# SMARTBALL_v2_1.net
KiCad netlist of a schematic drawn in EAGLE
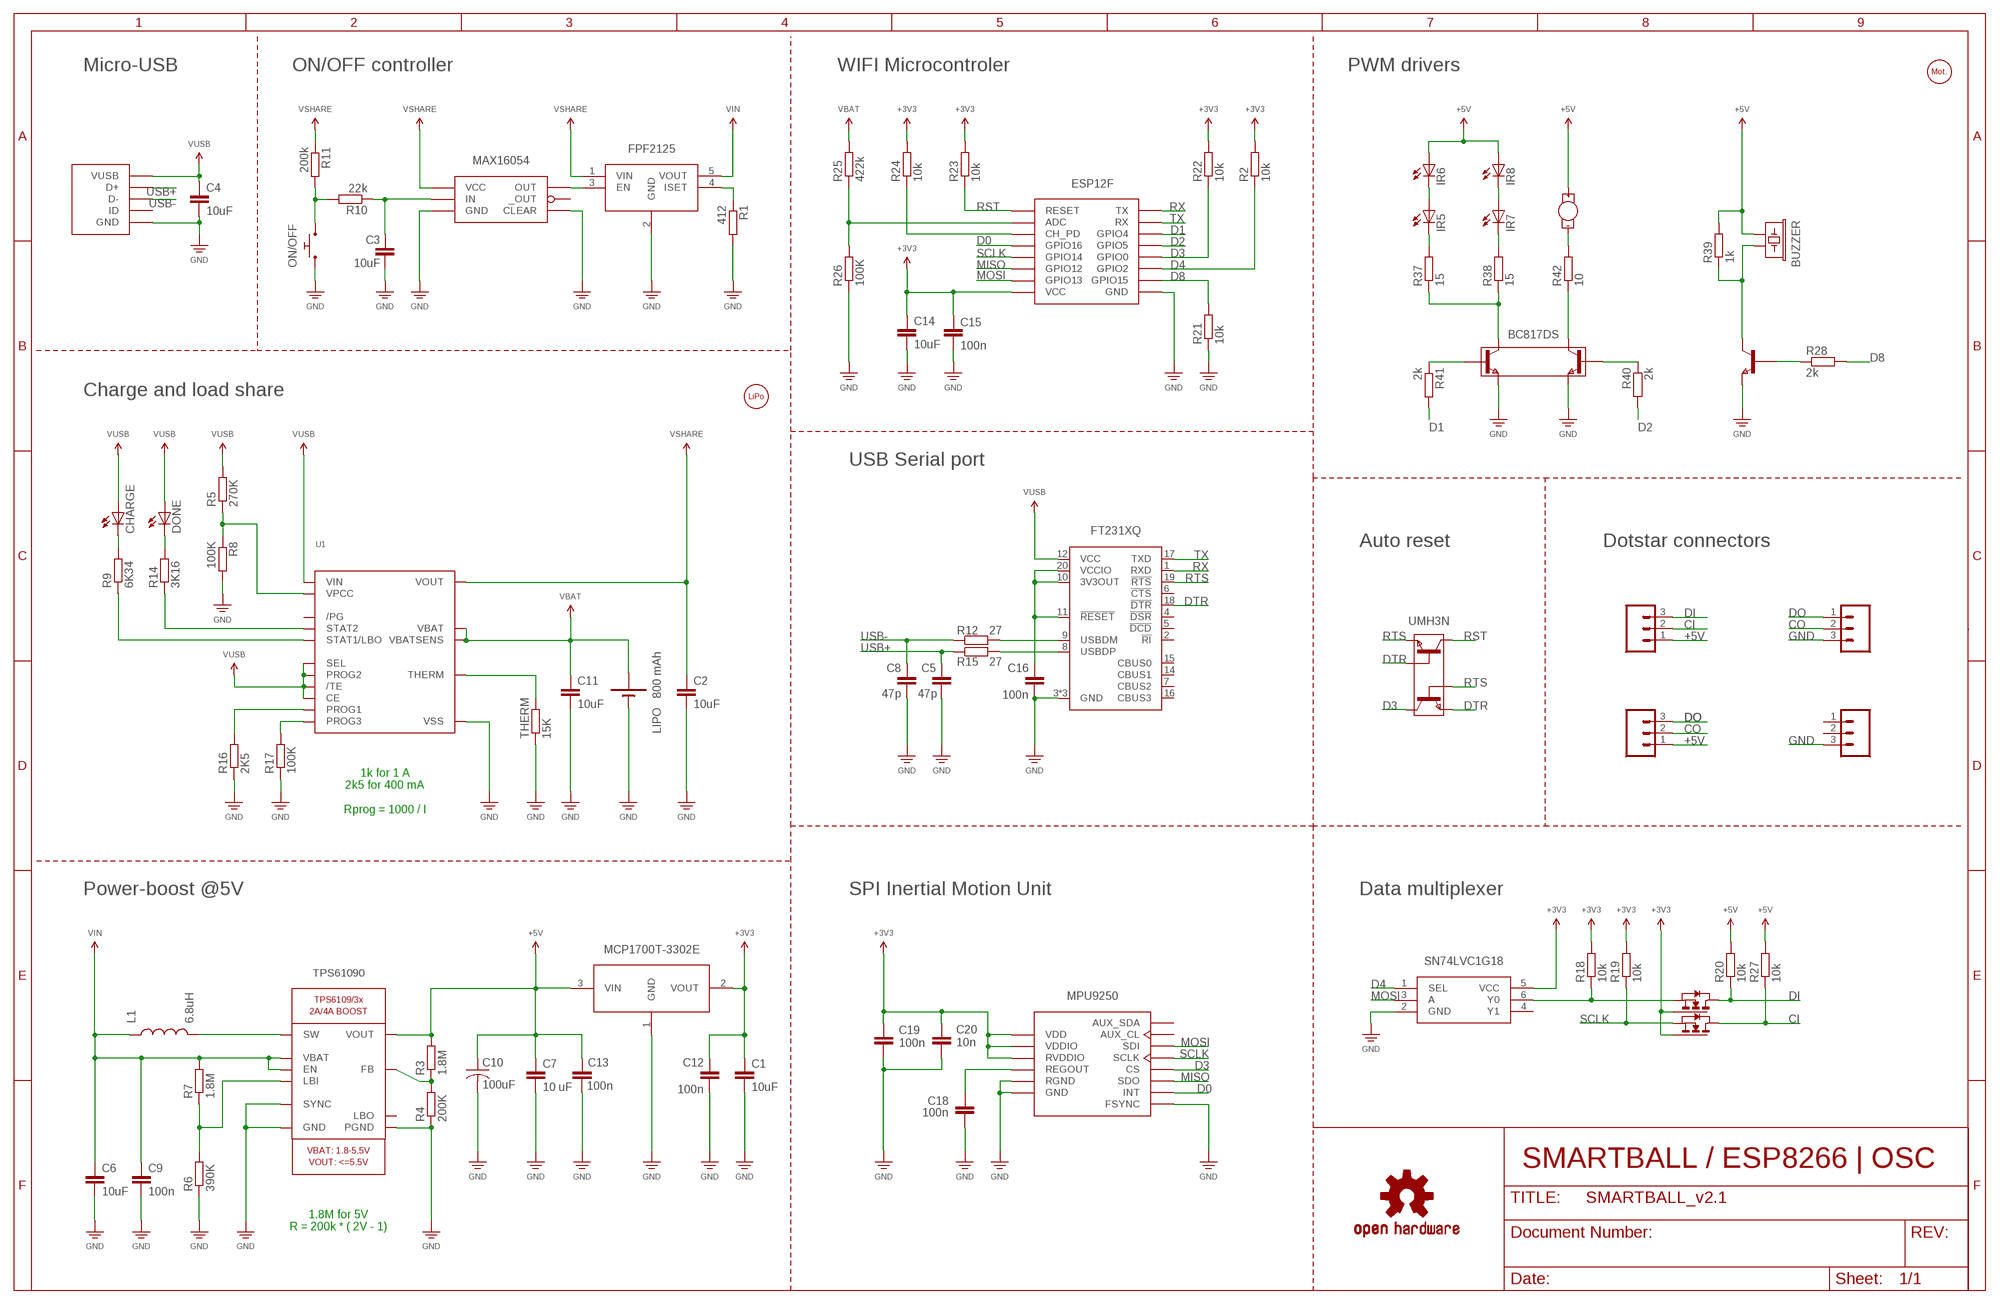
[diagram p0: schematic, sheet 1]

(export (version "E")
  (design (tool "Eeschema 10.0.6"))
  (components
    (comp (ref "BC817DS")
      (value "SOT_BC817DS")
      (footprint "eagle-import:SOT457R_PHILIPS")
      (libsource (lib "eagle-import") (part "SOT_BC817DS"))
    )
    (comp (ref "BUZZER")
      (value "BUZZER_PKMCS0909E4000-R1")
      (footprint "eagle-import:BUZZER_PKMCS0909E4000-R1")
      (libsource (lib "eagle-import") (part "BUZZER_PKMCS0909E4000-R1"))
    )
    (comp (ref "C1")
      (value "10uF")
      (footprint "eagle-import:C0603")
      (libsource (lib "eagle-import") (part "CAP_CERAMICC0603K"))
    )
    (comp (ref "C2")
      (value "10uF")
      (footprint "eagle-import:C0603")
      (libsource (lib "eagle-import") (part "CAP_CERAMICC0603K"))
    )
    (comp (ref "C3")
      (value "10uF")
      (footprint "eagle-import:C0603")
      (libsource (lib "eagle-import") (part "CAP_CERAMICC0603K"))
    )
    (comp (ref "C4")
      (value "10uF")
      (footprint "eagle-import:C0603")
      (libsource (lib "eagle-import") (part "CAP_CERAMICC0603K"))
    )
    (comp (ref "C5")
      (value "47p")
      (footprint "eagle-import:C0603")
      (libsource (lib "eagle-import") (part "CAP_CERAMICC0603K"))
    )
    (comp (ref "C6")
      (value "10uF")
      (footprint "eagle-import:C0603")
      (libsource (lib "eagle-import") (part "CAP_CERAMICC0603K"))
    )
    (comp (ref "C7")
      (value "10 uF")
      (footprint "eagle-import:C0603")
      (libsource (lib "eagle-import") (part "CAP_CERAMICC0603K"))
    )
    (comp (ref "C8")
      (value "47p")
      (footprint "eagle-import:C0603")
      (libsource (lib "eagle-import") (part "CAP_CERAMICC0603K"))
    )
    (comp (ref "C9")
      (value "100n")
      (footprint "eagle-import:C0603")
      (libsource (lib "eagle-import") (part "CAP_CERAMICC0603K"))
    )
    (comp (ref "C10")
      (value "100uF")
      (footprint "eagle-import:C1210")
      (libsource (lib "eagle-import") (part "CAP_TANTALUMC1210"))
    )
    (comp (ref "C11")
      (value "10uF")
      (footprint "eagle-import:C0603")
      (libsource (lib "eagle-import") (part "CAP_CERAMICC0603K"))
    )
    (comp (ref "C12")
      (value "100n")
      (footprint "eagle-import:C0603")
      (libsource (lib "eagle-import") (part "CAP_CERAMICC0603K"))
    )
    (comp (ref "C13")
      (value "100n")
      (footprint "eagle-import:C0603")
      (libsource (lib "eagle-import") (part "CAP_CERAMICC0603K"))
    )
    (comp (ref "C14")
      (value "10uF")
      (footprint "eagle-import:C0603")
      (libsource (lib "eagle-import") (part "CAP_CERAMICC0603K"))
    )
    (comp (ref "C15")
      (value "100n")
      (footprint "eagle-import:C0603")
      (libsource (lib "eagle-import") (part "CAP_CERAMICC0603K"))
    )
    (comp (ref "C16")
      (value "100n")
      (footprint "eagle-import:C0603")
      (libsource (lib "eagle-import") (part "CAP_CERAMICC0603K"))
    )
    (comp (ref "C18")
      (value "100n")
      (footprint "eagle-import:C0603")
      (libsource (lib "eagle-import") (part "CAP_CERAMICC0603K"))
    )
    (comp (ref "C19")
      (value "100n")
      (footprint "eagle-import:C0603")
      (libsource (lib "eagle-import") (part "CAP_CERAMICC0603K"))
    )
    (comp (ref "C20")
      (value "10n")
      (footprint "eagle-import:C0603")
      (libsource (lib "eagle-import") (part "CAP_CERAMICC0603K"))
    )
    (comp (ref "CHARGE")
      (value "LED_KINGBRIGHT_16X08")
      (footprint "eagle-import:LED_KINGBRIGHT_16X08")
      (libsource (lib "eagle-import") (part "LED_KINGBRIGHT_16X08"))
    )
    (comp (ref "DONE")
      (value "LED_KINGBRIGHT_16X08")
      (footprint "eagle-import:LED_KINGBRIGHT_16X08")
      (libsource (lib "eagle-import") (part "LED_KINGBRIGHT_16X08"))
    )
    (comp (ref "ESP12F")
      (value "µP_ESP12")
      (footprint "eagle-import:µP_ESP12")
      (libsource (lib "eagle-import") (part "µP_ESP12"))
    )
    (comp (ref "FT231XQ")
      (value "QFN_FT231X")
      (footprint "eagle-import:QFN20")
      (libsource (lib "eagle-import") (part "QFN_FT231X"))
    )
    (comp (ref "IR5")
      (value "LED_SFH4050")
      (footprint "eagle-import:LED_SFH4050")
      (libsource (lib "eagle-import") (part "LED_SFH4050"))
    )
    (comp (ref "IR6")
      (value "LED_SFH4050")
      (footprint "eagle-import:LED_SFH4050")
      (libsource (lib "eagle-import") (part "LED_SFH4050"))
    )
    (comp (ref "IR7")
      (value "LED_SFH4050")
      (footprint "eagle-import:LED_SFH4050")
      (libsource (lib "eagle-import") (part "LED_SFH4050"))
    )
    (comp (ref "IR8")
      (value "LED_SFH4050")
      (footprint "eagle-import:LED_SFH4050")
      (libsource (lib "eagle-import") (part "LED_SFH4050"))
    )
    (comp (ref "L1")
      (value "6.8uH")
      (footprint "eagle-import:IND_ASPIAIG-S4035")
      (libsource (lib "eagle-import") (part "IND_ASPIAIG-S4035"))
    )
    (comp (ref "LIPO")
      (value "CONN_BATTERY")
      (footprint "eagle-import:CONN_WIRES")
      (libsource (lib "eagle-import") (part "CONN_BATTERY"))
    )
    (comp (ref "LOGO1")
      (value "LOGO_OSHWL")
      (footprint "eagle-import:LOGO_OSHW")
      (libsource (lib "eagle-import") (part "LOGO_OSHWL"))
    )
    (comp (ref "MOTOR")
      (value "CONN_MOTOR")
      (footprint "eagle-import:CONN_WIRES")
      (libsource (lib "eagle-import") (part "CONN_MOTOR"))
    )
    (comp (ref "ON/OFF")
      (value "BUT_KMR6")
      (footprint "eagle-import:BUT_KMR6")
      (libsource (lib "eagle-import") (part "BUT_KMR6"))
    )
    (comp (ref "R1")
      (value "412")
      (footprint "eagle-import:R0402")
      (libsource (lib "eagle-import") (part "RES_EUR0402"))
    )
    (comp (ref "R2")
      (value "10k")
      (footprint "eagle-import:R0402")
      (libsource (lib "eagle-import") (part "RES_EUR0402"))
    )
    (comp (ref "R3")
      (value "1.8M")
      (footprint "eagle-import:R0402")
      (libsource (lib "eagle-import") (part "RES_EUR0402"))
    )
    (comp (ref "R4")
      (value "200K")
      (footprint "eagle-import:R0402")
      (libsource (lib "eagle-import") (part "RES_EUR0402"))
    )
    (comp (ref "R5")
      (value "270K")
      (footprint "eagle-import:R0402")
      (libsource (lib "eagle-import") (part "RES_EUR0402"))
    )
    (comp (ref "R6")
      (value "390K")
      (footprint "eagle-import:R0402")
      (libsource (lib "eagle-import") (part "RES_EUR0402"))
    )
    (comp (ref "R7")
      (value "1.8M")
      (footprint "eagle-import:R0402")
      (libsource (lib "eagle-import") (part "RES_EUR0402"))
    )
    (comp (ref "R8")
      (value "100K")
      (footprint "eagle-import:R0402")
      (libsource (lib "eagle-import") (part "RES_EUR0402"))
    )
    (comp (ref "R9")
      (value "6K34")
      (footprint "eagle-import:R0402")
      (libsource (lib "eagle-import") (part "RES_EUR0402"))
    )
    (comp (ref "R10")
      (value "22k")
      (footprint "eagle-import:R0402")
      (libsource (lib "eagle-import") (part "RES_EUR0402"))
    )
    (comp (ref "R11")
      (value "200k")
      (footprint "eagle-import:R0402")
      (libsource (lib "eagle-import") (part "RES_EUR0402"))
    )
    (comp (ref "R12")
      (value "27")
      (footprint "eagle-import:R0402")
      (libsource (lib "eagle-import") (part "RES_EUR0402"))
    )
    (comp (ref "R14")
      (value "3K16")
      (footprint "eagle-import:R0402")
      (libsource (lib "eagle-import") (part "RES_EUR0402"))
    )
    (comp (ref "R15")
      (value "27")
      (footprint "eagle-import:R0402")
      (libsource (lib "eagle-import") (part "RES_EUR0402"))
    )
    (comp (ref "R16")
      (value "2K5")
      (footprint "eagle-import:R0402")
      (libsource (lib "eagle-import") (part "RES_EUR0402"))
    )
    (comp (ref "R17")
      (value "100K")
      (footprint "eagle-import:R0402")
      (libsource (lib "eagle-import") (part "RES_EUR0402"))
    )
    (comp (ref "R18")
      (value "10k")
      (footprint "eagle-import:R0402")
      (libsource (lib "eagle-import") (part "RES_EUR0402"))
    )
    (comp (ref "R19")
      (value "10k")
      (footprint "eagle-import:R0402")
      (libsource (lib "eagle-import") (part "RES_EUR0402"))
    )
    (comp (ref "R20")
      (value "10k")
      (footprint "eagle-import:R0402")
      (libsource (lib "eagle-import") (part "RES_EUR0402"))
    )
    (comp (ref "R21")
      (value "10k")
      (footprint "eagle-import:R0402")
      (libsource (lib "eagle-import") (part "RES_EUR0402"))
    )
    (comp (ref "R22")
      (value "10k")
      (footprint "eagle-import:R0402")
      (libsource (lib "eagle-import") (part "RES_EUR0402"))
    )
    (comp (ref "R23")
      (value "10k")
      (footprint "eagle-import:R0402")
      (libsource (lib "eagle-import") (part "RES_EUR0402"))
    )
    (comp (ref "R24")
      (value "10k")
      (footprint "eagle-import:R0402")
      (libsource (lib "eagle-import") (part "RES_EUR0402"))
    )
    (comp (ref "R25")
      (value "422k")
      (footprint "eagle-import:R0402")
      (libsource (lib "eagle-import") (part "RES_EUR0402"))
    )
    (comp (ref "R26")
      (value "100K")
      (footprint "eagle-import:R0402")
      (libsource (lib "eagle-import") (part "RES_EUR0402"))
    )
    (comp (ref "R27")
      (value "10k")
      (footprint "eagle-import:R0402")
      (libsource (lib "eagle-import") (part "RES_EUR0402"))
    )
    (comp (ref "R28")
      (value "2k")
      (footprint "eagle-import:R0402")
      (libsource (lib "eagle-import") (part "RES_EUR0402"))
    )
    (comp (ref "R37")
      (value "15")
      (footprint "eagle-import:R0402")
      (libsource (lib "eagle-import") (part "RES_EUR0402"))
    )
    (comp (ref "R38")
      (value "15")
      (footprint "eagle-import:R0402")
      (libsource (lib "eagle-import") (part "RES_EUR0402"))
    )
    (comp (ref "R39")
      (value "1k")
      (footprint "eagle-import:R0402")
      (libsource (lib "eagle-import") (part "RES_EUR0402"))
    )
    (comp (ref "R40")
      (value "2k")
      (footprint "eagle-import:R0402")
      (libsource (lib "eagle-import") (part "RES_EUR0402"))
    )
    (comp (ref "R41")
      (value "2k")
      (footprint "eagle-import:R0402")
      (libsource (lib "eagle-import") (part "RES_EUR0402"))
    )
    (comp (ref "R42")
      (value "10")
      (footprint "eagle-import:R0402")
      (libsource (lib "eagle-import") (part "RES_EUR0402"))
    )
    (comp (ref "THERM")
      (value "15K")
      (footprint "eagle-import:R0402")
      (libsource (lib "eagle-import") (part "RES_EUR0402"))
    )
    (comp (ref "TPS61090")
      (value "TPS61090RSAR")
      (footprint "eagle-import:QFN16")
      (libsource (lib "eagle-import") (part "QFN_TPS6103X"))
    )
    (comp (ref "U$1")
      (value "CONN_USB")
      (footprint "eagle-import:CONN_USB")
      (libsource (lib "eagle-import") (part "CONN_USB"))
    )
    (comp (ref "U$2")
      (value "SOT_FPF2125")
      (footprint "eagle-import:SOT23-5")
      (libsource (lib "eagle-import") (part "SOT_FPF2125"))
    )
    (comp (ref "U$3")
      (value "SOT_MCP1700T")
      (footprint "eagle-import:SOT23-3")
      (libsource (lib "eagle-import") (part "SOT_MCP1700T"))
    )
    (comp (ref "U$5")
      (value "CONN_03_SMD")
      (footprint "eagle-import:CONN_03_SMD")
      (libsource (lib "eagle-import") (part "CONN_03_SMD"))
    )
    (comp (ref "U$6")
      (value "CONN_03_SMD")
      (footprint "eagle-import:CONN_03_SMD")
      (libsource (lib "eagle-import") (part "CONN_03_SMD"))
    )
    (comp (ref "U$12")
      (value "SOT_MAX16054")
      (footprint "eagle-import:TSOT23-6")
      (libsource (lib "eagle-import") (part "SOT_MAX16054"))
    )
    (comp (ref "U$14")
      (value "CONN_03_SMD")
      (footprint "eagle-import:CONN_03_SMD")
      (libsource (lib "eagle-import") (part "CONN_03_SMD"))
    )
    (comp (ref "U$15")
      (value "CONN_03_SMD")
      (footprint "eagle-import:CONN_03_SMD")
      (libsource (lib "eagle-import") (part "CONN_03_SMD"))
    )
    (comp (ref "U$19")
      (value "MOTOR_BODY")
      (footprint "eagle-import:MOTOR_BODY")
      (libsource (lib "eagle-import") (part "MOTOR_BODY"))
    )
    (comp (ref "U$20")
      (value "SOT_SN74LVC1G18")
      (footprint "eagle-import:SOT363")
      (libsource (lib "eagle-import") (part "SOT_SN74LVC1G18"))
    )
    (comp (ref "U$21")
      (value "QFN_MPU-9250QFN24G")
      (footprint "eagle-import:QFN24_3MM")
      (libsource (lib "eagle-import") (part "QFN_MPU-9250QFN24G"))
    )
    (comp (ref "U$22")
      (value "SOT_2N7002PS")
      (footprint "eagle-import:SOT363")
      (libsource (lib "eagle-import") (part "SOT_2N7002PS"))
    )
    (comp (ref "U$28")
      (value "SOT_SBC847AWT1G")
      (footprint "eagle-import:SOT323")
      (libsource (lib "eagle-import") (part "SOT_SBC847AWT1G"))
    )
    (comp (ref "U$29")
      (value "BATT_BODY")
      (footprint "eagle-import:BATT_BODY")
      (libsource (lib "eagle-import") (part "BATT_BODY"))
    )
    (comp (ref "U1")
      (value "QFN_MCP73871")
      (footprint "eagle-import:QFN20")
      (libsource (lib "eagle-import") (part "QFN_MCP73871"))
    )
    (comp (ref "UMH3N")
      (value "SOT_UMH3N")
      (footprint "eagle-import:SOT363")
      (libsource (lib "eagle-import") (part "SOT_UMH3N"))
    )
  )
  (nets
    (net (code "1") (name "+3V3") (class "Default")
      (node (ref "C1") (pin "1") (pinfunction "1_1") (pintype "passive"))
      (node (ref "C12") (pin "1") (pinfunction "1_1") (pintype "passive"))
      (node (ref "C14") (pin "1") (pinfunction "1_1") (pintype "passive"))
      (node (ref "C15") (pin "1") (pinfunction "1_1") (pintype "passive"))
      (node (ref "C19") (pin "1") (pinfunction "1_1") (pintype "passive"))
      (node (ref "C20") (pin "2") (pinfunction "2_2") (pintype "passive"))
      (node (ref "ESP12F") (pin "VCC") (pinfunction "VCC_VCC") (pintype "bidirectional"))
      (node (ref "R18") (pin "2") (pinfunction "2_2") (pintype "passive"))
      (node (ref "R19") (pin "2") (pinfunction "2_2") (pintype "passive"))
      (node (ref "R2") (pin "2") (pinfunction "2_2") (pintype "passive"))
      (node (ref "R22") (pin "2") (pinfunction "2_2") (pintype "passive"))
      (node (ref "R23") (pin "2") (pinfunction "2_2") (pintype "passive"))
      (node (ref "R24") (pin "2") (pinfunction "2_2") (pintype "passive"))
      (node (ref "U$20") (pin "5") (pinfunction "VCC_5") (pintype "bidirectional"))
      (node (ref "U$21") (pin "1") (pinfunction "RVDDIO_1") (pintype "bidirectional"))
      (node (ref "U$21") (pin "13") (pinfunction "VDD_13") (pintype "bidirectional"))
      (node (ref "U$21") (pin "8") (pinfunction "VDDIO_8") (pintype "bidirectional"))
      (node (ref "U$22") (pin "2") (pinfunction "G1_2") (pintype "passive"))
      (node (ref "U$22") (pin "5") (pinfunction "G2_5") (pintype "passive"))
      (node (ref "U$3") (pin "2") (pinfunction "VOUT_2") (pintype "bidirectional"))
    )
    (net (code "2") (name "+5V") (class "Default")
      (node (ref "BUZZER") (pin "1") (pinfunction "1_1") (pintype "passive"))
      (node (ref "C10") (pin "1") (pinfunction "1_1") (pintype "passive"))
      (node (ref "C13") (pin "1") (pinfunction "1_1") (pintype "passive"))
      (node (ref "C7") (pin "1") (pinfunction "1_1") (pintype "passive"))
      (node (ref "IR6") (pin "1") (pinfunction "A_1") (pintype "passive"))
      (node (ref "IR8") (pin "1") (pinfunction "A_1") (pintype "passive"))
      (node (ref "MOTOR") (pin "VCC") (pinfunction "+_VCC") (pintype "bidirectional"))
      (node (ref "R20") (pin "2") (pinfunction "2_2") (pintype "passive"))
      (node (ref "R27") (pin "2") (pinfunction "2_2") (pintype "passive"))
      (node (ref "R3") (pin "2") (pinfunction "2_2") (pintype "passive"))
      (node (ref "R39") (pin "2") (pinfunction "2_2") (pintype "passive"))
      (node (ref "TPS61090") (pin "1") (pinfunction "VOUT_1") (pintype "power_in"))
      (node (ref "TPS61090") (pin "15") (pinfunction "VOUT_15") (pintype "power_in"))
      (node (ref "TPS61090") (pin "16") (pinfunction "VOUT_16") (pintype "power_in"))
      (node (ref "U$15") (pin "1") (pinfunction "1_1") (pintype "passive"))
      (node (ref "U$3") (pin "3") (pinfunction "VIN_3") (pintype "bidirectional"))
      (node (ref "U$5") (pin "1") (pinfunction "1_1") (pintype "passive"))
    )
    (net (code "3") (name "/CI") (class "Default")
      (node (ref "R27") (pin "1") (pinfunction "1_1") (pintype "passive"))
      (node (ref "U$22") (pin "3") (pinfunction "D2_3") (pintype "passive"))
      (node (ref "U$5") (pin "2") (pinfunction "2_2") (pintype "passive"))
    )
    (net (code "4") (name "/CO") (class "Default")
      (node (ref "U$15") (pin "2") (pinfunction "2_2") (pintype "passive"))
      (node (ref "U$6") (pin "2") (pinfunction "2_2") (pintype "passive"))
    )
    (net (code "5") (name "/D0") (class "Default")
      (node (ref "ESP12F") (pin "GPIO16") (pinfunction "GPIO16_GPIO16") (pintype "bidirectional"))
      (node (ref "U$21") (pin "12") (pinfunction "INT_12") (pintype "bidirectional"))
    )
    (net (code "6") (name "/D1") (class "Default")
      (node (ref "ESP12F") (pin "GPIO4") (pinfunction "GPIO4_GPIO4") (pintype "bidirectional"))
      (node (ref "R41") (pin "2") (pinfunction "2_2") (pintype "passive"))
    )
    (net (code "7") (name "/D2") (class "Default")
      (node (ref "ESP12F") (pin "GPIO5") (pinfunction "GPIO5_GPIO5") (pintype "bidirectional"))
      (node (ref "R40") (pin "2") (pinfunction "2_2") (pintype "passive"))
    )
    (net (code "8") (name "/D3") (class "Default")
      (node (ref "ESP12F") (pin "GPIO0") (pinfunction "GPIO0_GPIO0") (pintype "bidirectional"))
      (node (ref "R22") (pin "1") (pinfunction "1_1") (pintype "passive"))
      (node (ref "U$21") (pin "22") (pinfunction "CS_22") (pintype "bidirectional"))
      (node (ref "UMH3N") (pin "3") (pinfunction "C2_3") (pintype "passive"))
    )
    (net (code "9") (name "/D4") (class "Default")
      (node (ref "ESP12F") (pin "GPIO2") (pinfunction "GPIO2_GPIO2") (pintype "bidirectional"))
      (node (ref "R2") (pin "1") (pinfunction "1_1") (pintype "passive"))
      (node (ref "U$20") (pin "1") (pinfunction "SEL_1") (pintype "bidirectional"))
    )
    (net (code "10") (name "/D8") (class "Default")
      (node (ref "ESP12F") (pin "GPIO15") (pinfunction "GPIO15_GPIO15") (pintype "bidirectional"))
      (node (ref "R21") (pin "2") (pinfunction "2_2") (pintype "passive"))
      (node (ref "R28") (pin "2") (pinfunction "2_2") (pintype "passive"))
    )
    (net (code "11") (name "/DI") (class "Default")
      (node (ref "R20") (pin "1") (pinfunction "1_1") (pintype "passive"))
      (node (ref "U$22") (pin "6") (pinfunction "D1_6") (pintype "passive"))
      (node (ref "U$5") (pin "3") (pinfunction "3_3") (pintype "passive"))
    )
    (net (code "12") (name "/DO") (class "Default")
      (node (ref "U$15") (pin "3") (pinfunction "3_3") (pintype "passive"))
      (node (ref "U$6") (pin "1") (pinfunction "1_1") (pintype "passive"))
    )
    (net (code "13") (name "/DTR") (class "Default")
      (node (ref "FT231XQ") (pin "18") (pinfunction "~{DTR}_18") (pintype "bidirectional"))
      (node (ref "UMH3N") (pin "2") (pinfunction "B1_2") (pintype "passive"))
      (node (ref "UMH3N") (pin "4") (pinfunction "E2_4") (pintype "passive"))
    )
    (net (code "14") (name "/MISO") (class "Default")
      (node (ref "ESP12F") (pin "GPIO12") (pinfunction "GPIO12_GPIO12") (pintype "bidirectional"))
      (node (ref "U$21") (pin "9") (pinfunction "SDO_9") (pintype "bidirectional"))
    )
    (net (code "15") (name "/MOSI") (class "Default")
      (node (ref "ESP12F") (pin "GPIO13") (pinfunction "GPIO13_GPIO13") (pintype "bidirectional"))
      (node (ref "U$20") (pin "3") (pinfunction "A_3") (pintype "bidirectional"))
      (node (ref "U$21") (pin "24") (pinfunction "SDI_24") (pintype "bidirectional"))
    )
    (net (code "16") (name "/RST") (class "Default")
      (node (ref "ESP12F") (pin "RESET") (pinfunction "RESET_RESET") (pintype "bidirectional"))
      (node (ref "R23") (pin "1") (pinfunction "1_1") (pintype "passive"))
      (node (ref "UMH3N") (pin "6") (pinfunction "C1_6") (pintype "passive"))
    )
    (net (code "17") (name "/RTS") (class "Default")
      (node (ref "FT231XQ") (pin "19") (pinfunction "~{RTS}_19") (pintype "bidirectional"))
      (node (ref "UMH3N") (pin "1") (pinfunction "E1_1") (pintype "passive"))
      (node (ref "UMH3N") (pin "5") (pinfunction "B2_5") (pintype "passive"))
    )
    (net (code "18") (name "/RX") (class "Default")
      (node (ref "ESP12F") (pin "TX") (pinfunction "TX_TX") (pintype "bidirectional"))
      (node (ref "FT231XQ") (pin "1") (pinfunction "RXD_1") (pintype "bidirectional"))
    )
    (net (code "19") (name "/SCLK") (class "Default")
      (node (ref "ESP12F") (pin "GPIO14") (pinfunction "GPIO14_GPIO14") (pintype "bidirectional"))
      (node (ref "R19") (pin "1") (pinfunction "1_1") (pintype "passive"))
      (node (ref "U$21") (pin "23") (pinfunction "SCLK_23") (pintype "bidirectional"))
      (node (ref "U$22") (pin "4") (pinfunction "S2_4") (pintype "passive"))
    )
    (net (code "20") (name "/TX") (class "Default")
      (node (ref "ESP12F") (pin "RX") (pinfunction "RX_RX") (pintype "bidirectional"))
      (node (ref "FT231XQ") (pin "17") (pinfunction "TXD_17") (pintype "bidirectional"))
    )
    (net (code "21") (name "/USB+") (class "Default")
      (node (ref "C5") (pin "1") (pinfunction "1_1") (pintype "passive"))
      (node (ref "R15") (pin "1") (pinfunction "1_1") (pintype "passive"))
      (node (ref "U$1") (pin "D+") (pinfunction "D+_D+") (pintype "bidirectional"))
    )
    (net (code "22") (name "/USB-") (class "Default")
      (node (ref "C8") (pin "1") (pinfunction "1_1") (pintype "passive"))
      (node (ref "R12") (pin "1") (pinfunction "1_1") (pintype "passive"))
      (node (ref "U$1") (pin "D-") (pinfunction "D-_D-") (pintype "bidirectional"))
    )
    (net (code "23") (name "GND") (class "Default")
      (node (ref "BC817DS") (pin "1") (pinfunction "E1_1") (pintype "passive"))
      (node (ref "BC817DS") (pin "4") (pinfunction "E2_4") (pintype "passive"))
      (node (ref "C1") (pin "2") (pinfunction "2_2") (pintype "passive"))
      (node (ref "C10") (pin "2") (pinfunction "2_2") (pintype "passive"))
      (node (ref "C11") (pin "2") (pinfunction "2_2") (pintype "passive"))
      (node (ref "C12") (pin "2") (pinfunction "2_2") (pintype "passive"))
      (node (ref "C13") (pin "2") (pinfunction "2_2") (pintype "passive"))
      (node (ref "C14") (pin "2") (pinfunction "2_2") (pintype "passive"))
      (node (ref "C15") (pin "2") (pinfunction "2_2") (pintype "passive"))
      (node (ref "C16") (pin "2") (pinfunction "2_2") (pintype "passive"))
      (node (ref "C18") (pin "2") (pinfunction "2_2") (pintype "passive"))
      (node (ref "C19") (pin "2") (pinfunction "2_2") (pintype "passive"))
      (node (ref "C2") (pin "2") (pinfunction "2_2") (pintype "passive"))
      (node (ref "C20") (pin "1") (pinfunction "1_1") (pintype "passive"))
      (node (ref "C3") (pin "2") (pinfunction "2_2") (pintype "passive"))
      (node (ref "C4") (pin "2") (pinfunction "2_2") (pintype "passive"))
      (node (ref "C5") (pin "2") (pinfunction "2_2") (pintype "passive"))
      (node (ref "C6") (pin "2") (pinfunction "2_2") (pintype "passive"))
      (node (ref "C7") (pin "2") (pinfunction "2_2") (pintype "passive"))
      (node (ref "C8") (pin "2") (pinfunction "2_2") (pintype "passive"))
      (node (ref "C9") (pin "2") (pinfunction "2_2") (pintype "passive"))
      (node (ref "ESP12F") (pin "GND") (pinfunction "GND_GND") (pintype "bidirectional"))
      (node (ref "FT231XQ") (pin "13") (pinfunction "GND_13") (pintype "bidirectional"))
      (node (ref "FT231XQ") (pin "3") (pinfunction "GND_3") (pintype "bidirectional"))
      (node (ref "FT231XQ") (pin "EXP") (pinfunction "GND_EXP") (pintype "bidirectional"))
      (node (ref "LIPO") (pin "GND") (pinfunction "GND_GND") (pintype "power_in"))
      (node (ref "ON/OFF") (pin "1") (pinfunction "1_1") (pintype "passive"))
      (node (ref "ON/OFF") (pin "4") (pinfunction "1_4") (pintype "passive"))
      (node (ref "R1") (pin "2") (pinfunction "2_2") (pintype "passive"))
      (node (ref "R16") (pin "1") (pinfunction "1_1") (pintype "passive"))
      (node (ref "R17") (pin "1") (pinfunction "1_1") (pintype "passive"))
      (node (ref "R21") (pin "1") (pinfunction "1_1") (pintype "passive"))
      (node (ref "R26") (pin "1") (pinfunction "1_1") (pintype "passive"))
      (node (ref "R4") (pin "1") (pinfunction "1_1") (pintype "passive"))
      (node (ref "R6") (pin "1") (pinfunction "1_1") (pintype "passive"))
      (node (ref "R8") (pin "2") (pinfunction "2_2") (pintype "passive"))
      (node (ref "THERM") (pin "1") (pinfunction "1_1") (pintype "passive"))
      (node (ref "TPS61090") (pin "10") (pinfunction "SYNC_10") (pintype "input"))
      (node (ref "TPS61090") (pin "13") (pinfunction "GND_13") (pintype "power_in"))
      (node (ref "TPS61090") (pin "5") (pinfunction "PGND_5") (pintype "power_in"))
      (node (ref "TPS61090") (pin "6") (pinfunction "PGND_6") (pintype "power_in"))
      (node (ref "TPS61090") (pin "7") (pinfunction "PGND_7") (pintype "power_in"))
      (node (ref "TPS61090") (pin "PAD") (pinfunction "PGND_PAD") (pintype "power_in"))
      (node (ref "U$1") (pin "GND") (pinfunction "GND_GND") (pintype "bidirectional"))
      (node (ref "U$1") (pin "P$1") (pinfunction "GND_P$1") (pintype "bidirectional"))
      (node (ref "U$1") (pin "P$11") (pinfunction "GND_P$11") (pintype "bidirectional"))
      (node (ref "U$1") (pin "SHELL1") (pinfunction "GND_SHELL1") (pintype "bidirectional"))
      (node (ref "U$1") (pin "SHELL2") (pinfunction "GND_SHELL2") (pintype "bidirectional"))
      (node (ref "U$1") (pin "SHELL5") (pinfunction "GND_SHELL5") (pintype "bidirectional"))
      (node (ref "U$1") (pin "SHELL6") (pinfunction "GND_SHELL6") (pintype "bidirectional"))
      (node (ref "U$12") (pin "2") (pinfunction "GND_2") (pintype "bidirectional"))
      (node (ref "U$12") (pin "3") (pinfunction "CLEAR_3") (pintype "bidirectional"))
      (node (ref "U$14") (pin "3") (pinfunction "3_3") (pintype "passive"))
      (node (ref "U$2") (pin "2") (pinfunction "GND_2") (pintype "bidirectional"))
      (node (ref "U$20") (pin "2") (pinfunction "GND_2") (pintype "bidirectional"))
      (node (ref "U$21") (pin "11") (pinfunction "FSYNC_11") (pintype "bidirectional"))
      (node (ref "U$21") (pin "18") (pinfunction "GND_18") (pintype "bidirectional"))
      (node (ref "U$21") (pin "20") (pinfunction "RGND_20") (pintype "bidirectional"))
      (node (ref "U$28") (pin "2") (pinfunction "E_2") (pintype "passive"))
      (node (ref "U$3") (pin "1") (pinfunction "GND_1") (pintype "bidirectional"))
      (node (ref "U$6") (pin "3") (pinfunction "3_3") (pintype "passive"))
      (node (ref "U1") (pin "10") (pinfunction "VSS_10") (pintype "bidirectional"))
      (node (ref "U1") (pin "11") (pinfunction "VSS_11") (pintype "bidirectional"))
      (node (ref "U1") (pin "EXP") (pinfunction "VSS_EXP") (pintype "bidirectional"))
    )
    (net (code "24") (name "Net-(BC817DS-B1)") (class "Default")
      (node (ref "BC817DS") (pin "2") (pinfunction "B1_2") (pintype "passive"))
      (node (ref "R40") (pin "1") (pinfunction "1_1") (pintype "passive"))
    )
    (net (code "25") (name "Net-(BC817DS-B2)") (class "Default")
      (node (ref "BC817DS") (pin "5") (pinfunction "B2_5") (pintype "passive"))
      (node (ref "R41") (pin "1") (pinfunction "1_1") (pintype "passive"))
    )
    (net (code "26") (name "Net-(BC817DS-C1)") (class "Default")
      (node (ref "BC817DS") (pin "6") (pinfunction "C1_6") (pintype "passive"))
      (node (ref "R42") (pin "1") (pinfunction "1_1") (pintype "passive"))
    )
    (net (code "27") (name "Net-(BC817DS-C2)") (class "Default")
      (node (ref "BC817DS") (pin "3") (pinfunction "C2_3") (pintype "passive"))
      (node (ref "R37") (pin "1") (pinfunction "1_1") (pintype "passive"))
      (node (ref "R38") (pin "1") (pinfunction "1_1") (pintype "passive"))
    )
    (net (code "28") (name "Net-(CHARGE-C)") (class "Default")
      (node (ref "CHARGE") (pin "2") (pinfunction "C_2") (pintype "passive"))
      (node (ref "R9") (pin "2") (pinfunction "2_2") (pintype "passive"))
    )
    (net (code "29") (name "Net-(DONE-C)") (class "Default")
      (node (ref "DONE") (pin "2") (pinfunction "C_2") (pintype "passive"))
      (node (ref "R14") (pin "2") (pinfunction "2_2") (pintype "passive"))
    )
    (net (code "30") (name "Net-(ESP12F-PadADC)") (class "Default")
      (node (ref "ESP12F") (pin "ADC") (pinfunction "ADC_ADC") (pintype "bidirectional"))
      (node (ref "R25") (pin "1") (pinfunction "1_1") (pintype "passive"))
      (node (ref "R26") (pin "2") (pinfunction "2_2") (pintype "passive"))
    )
    (net (code "31") (name "Net-(ESP12F-PadCH_PD)") (class "Default")
      (node (ref "ESP12F") (pin "CH_PD") (pinfunction "CH_PD_CH_PD") (pintype "bidirectional"))
      (node (ref "R24") (pin "1") (pinfunction "1_1") (pintype "passive"))
    )
    (net (code "32") (name "Net-(FT231XQ-3V3OUT)") (class "Default")
      (node (ref "C16") (pin "1") (pinfunction "1_1") (pintype "passive"))
      (node (ref "FT231XQ") (pin "10") (pinfunction "3V3OUT_10") (pintype "bidirectional"))
      (node (ref "FT231XQ") (pin "11") (pinfunction "~{RESET}_11") (pintype "bidirectional"))
      (node (ref "FT231XQ") (pin "20") (pinfunction "VCCIO_20") (pintype "bidirectional"))
    )
    (net (code "33") (name "Net-(FT231XQ-USBDM)") (class "Default")
      (node (ref "FT231XQ") (pin "9") (pinfunction "USBDM_9") (pintype "bidirectional"))
      (node (ref "R12") (pin "2") (pinfunction "2_2") (pintype "passive"))
    )
    (net (code "34") (name "Net-(FT231XQ-USBDP)") (class "Default")
      (node (ref "FT231XQ") (pin "8") (pinfunction "USBDP_8") (pintype "bidirectional"))
      (node (ref "R15") (pin "2") (pinfunction "2_2") (pintype "passive"))
    )
    (net (code "35") (name "Net-(IR5-A)") (class "Default")
      (node (ref "IR5") (pin "1") (pinfunction "A_1") (pintype "passive"))
      (node (ref "IR6") (pin "2") (pinfunction "C_2") (pintype "passive"))
    )
    (net (code "36") (name "Net-(IR5-C)") (class "Default")
      (node (ref "IR5") (pin "2") (pinfunction "C_2") (pintype "passive"))
      (node (ref "R37") (pin "2") (pinfunction "2_2") (pintype "passive"))
    )
    (net (code "37") (name "Net-(IR7-A)") (class "Default")
      (node (ref "IR7") (pin "1") (pinfunction "A_1") (pintype "passive"))
      (node (ref "IR8") (pin "2") (pinfunction "C_2") (pintype "passive"))
    )
    (net (code "38") (name "Net-(IR7-C)") (class "Default")
      (node (ref "IR7") (pin "2") (pinfunction "C_2") (pintype "passive"))
      (node (ref "R38") (pin "2") (pinfunction "2_2") (pintype "passive"))
    )
    (net (code "39") (name "Net-(L1-Pad2)") (class "Default")
      (node (ref "L1") (pin "2") (pinfunction "2_2") (pintype "passive"))
      (node (ref "TPS61090") (pin "3") (pinfunction "SW_3") (pintype "input"))
      (node (ref "TPS61090") (pin "4") (pinfunction "SW_4") (pintype "input"))
    )
    (net (code "40") (name "Net-(MOTOR--)") (class "Default")
      (node (ref "MOTOR") (pin "GND") (pinfunction "-_GND") (pintype "bidirectional"))
      (node (ref "R42") (pin "2") (pinfunction "2_2") (pintype "passive"))
    )
    (net (code "41") (name "Net-(ON/OFF-2-Pad3)") (class "Default")
      (node (ref "ON/OFF") (pin "2") (pinfunction "2_2") (pintype "passive"))
      (node (ref "ON/OFF") (pin "3") (pinfunction "2_3") (pintype "passive"))
      (node (ref "R10") (pin "2") (pinfunction "2_2") (pintype "passive"))
      (node (ref "R11") (pin "2") (pinfunction "2_2") (pintype "passive"))
    )
    (net (code "42") (name "Net-(TPS61090-FB)") (class "Default")
      (node (ref "R3") (pin "1") (pinfunction "1_1") (pintype "passive"))
      (node (ref "R4") (pin "2") (pinfunction "2_2") (pintype "passive"))
      (node (ref "TPS61090") (pin "14") (pinfunction "FB_14") (pintype "input"))
    )
    (net (code "43") (name "Net-(TPS61090-LBI)") (class "Default")
      (node (ref "R6") (pin "2") (pinfunction "2_2") (pintype "passive"))
      (node (ref "R7") (pin "1") (pinfunction "1_1") (pintype "passive"))
      (node (ref "TPS61090") (pin "9") (pinfunction "LBI_9") (pintype "input"))
    )
    (net (code "44") (name "Net-(U$2-ISET)") (class "Default")
      (node (ref "R1") (pin "1") (pinfunction "1_1") (pintype "passive"))
      (node (ref "U$2") (pin "4") (pinfunction "ISET_4") (pintype "bidirectional"))
    )
    (net (code "45") (name "Net-(U$12-IN)") (class "Default")
      (node (ref "C3") (pin "1") (pinfunction "1_1") (pintype "passive"))
      (node (ref "R10") (pin "1") (pinfunction "1_1") (pintype "passive"))
      (node (ref "U$12") (pin "1") (pinfunction "IN_1") (pintype "bidirectional"))
    )
    (net (code "46") (name "Net-(U$12-OUT)") (class "Default")
      (node (ref "U$12") (pin "5") (pinfunction "OUT_5") (pintype "bidirectional"))
      (node (ref "U$2") (pin "3") (pinfunction "EN_3") (pintype "bidirectional"))
    )
    (net (code "47") (name "Net-(U$20-Y0)") (class "Default")
      (node (ref "R18") (pin "1") (pinfunction "1_1") (pintype "passive"))
      (node (ref "U$20") (pin "6") (pinfunction "Y0_6") (pintype "bidirectional"))
      (node (ref "U$22") (pin "1") (pinfunction "S1_1") (pintype "passive"))
    )
    (net (code "48") (name "Net-(U$21-REGOUT)") (class "Default")
      (node (ref "C18") (pin "1") (pinfunction "1_1") (pintype "passive"))
      (node (ref "U$21") (pin "10") (pinfunction "REGOUT_10") (pintype "bidirectional"))
    )
    (net (code "49") (name "Net-(U$28-B)") (class "Default")
      (node (ref "R28") (pin "1") (pinfunction "1_1") (pintype "passive"))
      (node (ref "U$28") (pin "1") (pinfunction "B_1") (pintype "passive"))
    )
    (net (code "50") (name "Net-(U$28-C)") (class "Default")
      (node (ref "BUZZER") (pin "2") (pinfunction "2_2") (pintype "passive"))
      (node (ref "R39") (pin "1") (pinfunction "1_1") (pintype "passive"))
      (node (ref "U$28") (pin "3") (pinfunction "C_3") (pintype "passive"))
    )
    (net (code "51") (name "Net-(U1-PROG1)") (class "Default")
      (node (ref "R16") (pin "2") (pinfunction "2_2") (pintype "passive"))
      (node (ref "U1") (pin "13") (pinfunction "PROG1_13") (pintype "bidirectional"))
    )
    (net (code "52") (name "Net-(U1-PROG3)") (class "Default")
      (node (ref "R17") (pin "2") (pinfunction "2_2") (pintype "passive"))
      (node (ref "U1") (pin "12") (pinfunction "PROG3_12") (pintype "bidirectional"))
    )
    (net (code "53") (name "Net-(U1-STAT1{slash}LBO)") (class "Default")
      (node (ref "R9") (pin "1") (pinfunction "1_1") (pintype "passive"))
      (node (ref "U1") (pin "8") (pinfunction "STAT1/LBO_8") (pintype "bidirectional"))
    )
    (net (code "54") (name "Net-(U1-STAT2)") (class "Default")
      (node (ref "R14") (pin "1") (pinfunction "1_1") (pintype "passive"))
      (node (ref "U1") (pin "7") (pinfunction "STAT2_7") (pintype "bidirectional"))
    )
    (net (code "55") (name "Net-(U1-THERM)") (class "Default")
      (node (ref "THERM") (pin "2") (pinfunction "2_2") (pintype "passive"))
      (node (ref "U1") (pin "5") (pinfunction "THERM_5") (pintype "bidirectional"))
    )
    (net (code "56") (name "Net-(U1-VPCC)") (class "Default")
      (node (ref "R5") (pin "1") (pinfunction "1_1") (pintype "passive"))
      (node (ref "R8") (pin "1") (pinfunction "1_1") (pintype "passive"))
      (node (ref "U1") (pin "2") (pinfunction "VPCC_2") (pintype "bidirectional"))
    )
    (net (code "57") (name "VBAT") (class "Default")
      (node (ref "C11") (pin "1") (pinfunction "1_1") (pintype "passive"))
      (node (ref "LIPO") (pin "VCC") (pinfunction "VBAT_VCC") (pintype "power_in"))
      (node (ref "R25") (pin "2") (pinfunction "2_2") (pintype "passive"))
      (node (ref "U1") (pin "14") (pinfunction "VBAT_14") (pintype "bidirectional"))
      (node (ref "U1") (pin "15") (pinfunction "VBAT_15") (pintype "bidirectional"))
      (node (ref "U1") (pin "16") (pinfunction "VBATSENS_16") (pintype "bidirectional"))
    )
    (net (code "58") (name "VIN") (class "Default")
      (node (ref "C6") (pin "1") (pinfunction "1_1") (pintype "passive"))
      (node (ref "C9") (pin "1") (pinfunction "1_1") (pintype "passive"))
      (node (ref "L1") (pin "1") (pinfunction "1_1") (pintype "passive"))
      (node (ref "R7") (pin "2") (pinfunction "2_2") (pintype "passive"))
      (node (ref "TPS61090") (pin "11") (pinfunction "EN_11") (pintype "input"))
      (node (ref "TPS61090") (pin "8") (pinfunction "VBAT_8") (pintype "input"))
      (node (ref "U$2") (pin "5") (pinfunction "VOUT_5") (pintype "bidirectional"))
    )
    (net (code "59") (name "VSHARE") (class "Default")
      (node (ref "C2") (pin "1") (pinfunction "1_1") (pintype "passive"))
      (node (ref "R11") (pin "1") (pinfunction "1_1") (pintype "passive"))
      (node (ref "U$12") (pin "6") (pinfunction "VCC_6") (pintype "bidirectional"))
      (node (ref "U$2") (pin "1") (pinfunction "VIN_1") (pintype "bidirectional"))
      (node (ref "U1") (pin "1") (pinfunction "VOUT_1") (pintype "bidirectional"))
      (node (ref "U1") (pin "20") (pinfunction "VOUT_20") (pintype "bidirectional"))
    )
    (net (code "60") (name "VUSB") (class "Default")
      (node (ref "C4") (pin "1") (pinfunction "1_1") (pintype "passive"))
      (node (ref "CHARGE") (pin "1") (pinfunction "A_1") (pintype "passive"))
      (node (ref "DONE") (pin "1") (pinfunction "A_1") (pintype "passive"))
      (node (ref "FT231XQ") (pin "12") (pinfunction "VCC_12") (pintype "bidirectional"))
      (node (ref "R5") (pin "2") (pinfunction "2_2") (pintype "passive"))
      (node (ref "U$1") (pin "VUSB") (pinfunction "VUSB_VUSB") (pintype "bidirectional"))
      (node (ref "U1") (pin "17") (pinfunction "CE_17") (pintype "bidirectional"))
      (node (ref "U1") (pin "18") (pinfunction "VIN_18") (pintype "bidirectional"))
      (node (ref "U1") (pin "19") (pinfunction "VIN_19") (pintype "bidirectional"))
      (node (ref "U1") (pin "3") (pinfunction "SEL_3") (pintype "bidirectional"))
      (node (ref "U1") (pin "4") (pinfunction "PROG2_4") (pintype "bidirectional"))
      (node (ref "U1") (pin "9") (pinfunction "/TE_9") (pintype "bidirectional"))
    )
    (net (code "61") (name "unconnected-(FT231XQ-CBUS0-Pad15)") (class "Default")
      (node (ref "FT231XQ") (pin "15") (pinfunction "CBUS0_15") (pintype "bidirectional"))
    )
    (net (code "62") (name "unconnected-(FT231XQ-CBUS1-Pad14)") (class "Default")
      (node (ref "FT231XQ") (pin "14") (pinfunction "CBUS1_14") (pintype "bidirectional"))
    )
    (net (code "63") (name "unconnected-(FT231XQ-CBUS2-Pad7)") (class "Default")
      (node (ref "FT231XQ") (pin "7") (pinfunction "CBUS2_7") (pintype "bidirectional"))
    )
    (net (code "64") (name "unconnected-(FT231XQ-CBUS3-Pad16)") (class "Default")
      (node (ref "FT231XQ") (pin "16") (pinfunction "CBUS3_16") (pintype "bidirectional"))
    )
    (net (code "65") (name "unconnected-(FT231XQ-~{CTS}-Pad6)") (class "Default")
      (node (ref "FT231XQ") (pin "6") (pinfunction "~{CTS}_6") (pintype "bidirectional"))
    )
    (net (code "66") (name "unconnected-(FT231XQ-~{DCD}-Pad5)") (class "Default")
      (node (ref "FT231XQ") (pin "5") (pinfunction "~{DCD}_5") (pintype "bidirectional"))
    )
    (net (code "67") (name "unconnected-(FT231XQ-~{DSR}-Pad4)") (class "Default")
      (node (ref "FT231XQ") (pin "4") (pinfunction "~{DSR}_4") (pintype "bidirectional"))
    )
    (net (code "68") (name "unconnected-(FT231XQ-~{RI}-Pad2)") (class "Default")
      (node (ref "FT231XQ") (pin "2") (pinfunction "~{RI}_2") (pintype "bidirectional"))
    )
    (net (code "69") (name "unconnected-(TPS61090-LBO-Pad12)") (class "Default")
      (node (ref "TPS61090") (pin "12") (pinfunction "LBO_12") (pintype "output"))
    )
    (net (code "70") (name "unconnected-(U$1-PadID)") (class "Default")
      (node (ref "U$1") (pin "ID") (pinfunction "ID_ID") (pintype "bidirectional"))
    )
    (net (code "71") (name "unconnected-(U$12-_OUT-Pad4)") (class "Default")
      (node (ref "U$12") (pin "4") (pinfunction "_OUT_4") (pintype "bidirectional"))
    )
    (net (code "72") (name "unconnected-(U$14-Pad1)") (class "Default")
      (node (ref "U$14") (pin "1") (pinfunction "1_1") (pintype "passive"))
    )
    (net (code "73") (name "unconnected-(U$14-Pad2)") (class "Default")
      (node (ref "U$14") (pin "2") (pinfunction "2_2") (pintype "passive"))
    )
    (net (code "74") (name "unconnected-(U$20-Y1-Pad4)") (class "Default")
      (node (ref "U$20") (pin "4") (pinfunction "Y1_4") (pintype "bidirectional"))
    )
    (net (code "75") (name "unconnected-(U$21-AUX_CL-Pad7)") (class "Default")
      (node (ref "U$21") (pin "7") (pinfunction "AUX_CL_7") (pintype "bidirectional"))
    )
    (net (code "76") (name "unconnected-(U$21-AUX_SDA-Pad21)") (class "Default")
      (node (ref "U$21") (pin "21") (pinfunction "AUX_SDA_21") (pintype "bidirectional"))
    )
    (net (code "77") (name "unconnected-(U1-{slash}PG-Pad6)") (class "Default")
      (node (ref "U1") (pin "6") (pinfunction "/PG_6") (pintype "bidirectional"))
    )
  )
)
